# Indication.net
KiCad netlist of a schematic drawn in Altium Designer
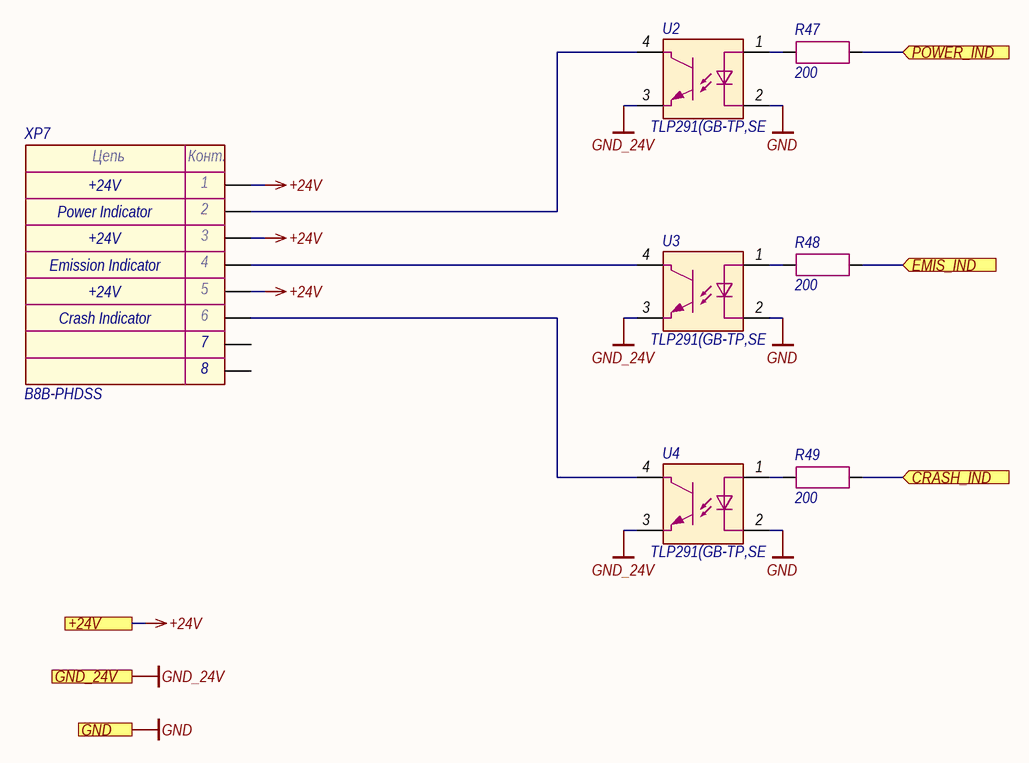
[diagram p0: Indication.SchDoc]

(export (version "E")
  (design (tool "Eeschema 10.0.6"))
  (components
    (comp (ref "R47")
      (value "200")
      (footprint "Pcb_library:RES_0603")
      (fields (field (name "MANUFACTURER") "Yageo"))
      (libsource (lib "Schem_library") (part "Resistor"))
    )
    (comp (ref "R48")
      (value "200")
      (footprint "Pcb_library:RES_0603")
      (fields (field (name "MANUFACTURER") "Yageo"))
      (libsource (lib "Schem_library") (part "Resistor"))
    )
    (comp (ref "R49")
      (value "200")
      (footprint "Pcb_library:RES_0603")
      (fields (field (name "MANUFACTURER") "Yageo"))
      (libsource (lib "Schem_library") (part "Resistor"))
    )
    (comp (ref "U2")
      (value "TLP291(GB-TP,SE")
      (footprint "Pcb_library:11-3C1")
      (fields (field (name "MANUFACTURER") "Toshiba"))
      (libsource (lib "Schem_library") (part "TLP291"))
    )
    (comp (ref "U3")
      (value "TLP291(GB-TP,SE")
      (footprint "Pcb_library:11-3C1")
      (fields (field (name "MANUFACTURER") "Toshiba"))
      (libsource (lib "Schem_library") (part "TLP291"))
    )
    (comp (ref "U4")
      (value "TLP291(GB-TP,SE")
      (footprint "Pcb_library:11-3C1")
      (fields (field (name "MANUFACTURER") "Toshiba"))
      (libsource (lib "Schem_library") (part "TLP291"))
    )
    (comp (ref "XP7")
      (value "B8B-PHDSS")
      (footprint "Pcb_library:B8B-PHDSS")
      (fields (field (name "MANUFACTURER") "JST"))
      (libsource (lib "Schem_library") (part "Connector-8"))
    )
  )
  (nets
    (net (code "1") (name "+24V") (class "Default")
      (node (ref "XP7") (pin "1") (pintype "passive"))
      (node (ref "XP7") (pin "3") (pintype "passive"))
      (node (ref "XP7") (pin "5") (pintype "passive"))
    )
    (net (code "2") (name "/CRASH_IND") (class "Default")
      (node (ref "R49") (pin "2") (pinfunction "2_2") (pintype "passive"))
    )
    (net (code "3") (name "/EMIS_IND") (class "Default")
      (node (ref "R48") (pin "2") (pinfunction "2_2") (pintype "passive"))
    )
    (net (code "4") (name "/POWER_IND") (class "Default")
      (node (ref "R47") (pin "2") (pinfunction "2_2") (pintype "passive"))
    )
    (net (code "5") (name "GND") (class "Default")
      (node (ref "U2") (pin "2") (pintype "passive"))
      (node (ref "U3") (pin "2") (pintype "passive"))
      (node (ref "U4") (pin "2") (pintype "passive"))
    )
    (net (code "6") (name "GND_24V") (class "Default")
      (node (ref "U2") (pin "3") (pintype "passive"))
      (node (ref "U3") (pin "3") (pintype "passive"))
      (node (ref "U4") (pin "3") (pintype "passive"))
    )
    (net (code "7") (name "Net-(R47-Pad1)") (class "Default")
      (node (ref "R47") (pin "1") (pinfunction "1_1") (pintype "passive"))
      (node (ref "U2") (pin "1") (pintype "passive"))
    )
    (net (code "8") (name "Net-(R48-Pad1)") (class "Default")
      (node (ref "R48") (pin "1") (pinfunction "1_1") (pintype "passive"))
      (node (ref "U3") (pin "1") (pintype "passive"))
    )
    (net (code "9") (name "Net-(R49-Pad1)") (class "Default")
      (node (ref "R49") (pin "1") (pinfunction "1_1") (pintype "passive"))
      (node (ref "U4") (pin "1") (pintype "passive"))
    )
    (net (code "10") (name "Net-(U2-Pad4)") (class "Default")
      (node (ref "U2") (pin "4") (pintype "passive"))
      (node (ref "XP7") (pin "2") (pintype "passive"))
    )
    (net (code "11") (name "Net-(U3-Pad4)") (class "Default")
      (node (ref "U3") (pin "4") (pintype "passive"))
      (node (ref "XP7") (pin "4") (pintype "passive"))
    )
    (net (code "12") (name "Net-(U4-Pad4)") (class "Default")
      (node (ref "U4") (pin "4") (pintype "passive"))
      (node (ref "XP7") (pin "6") (pintype "passive"))
    )
    (net (code "13") (name "unconnected-(XP7-Pad7)") (class "Default")
      (node (ref "XP7") (pin "7") (pintype "passive"))
    )
    (net (code "14") (name "unconnected-(XP7-Pad8)") (class "Default")
      (node (ref "XP7") (pin "8") (pintype "passive"))
    )
  )
)
